# LEGO_VL53L1X_Sensor.net
KiCad netlist of a schematic drawn in Altium Designer
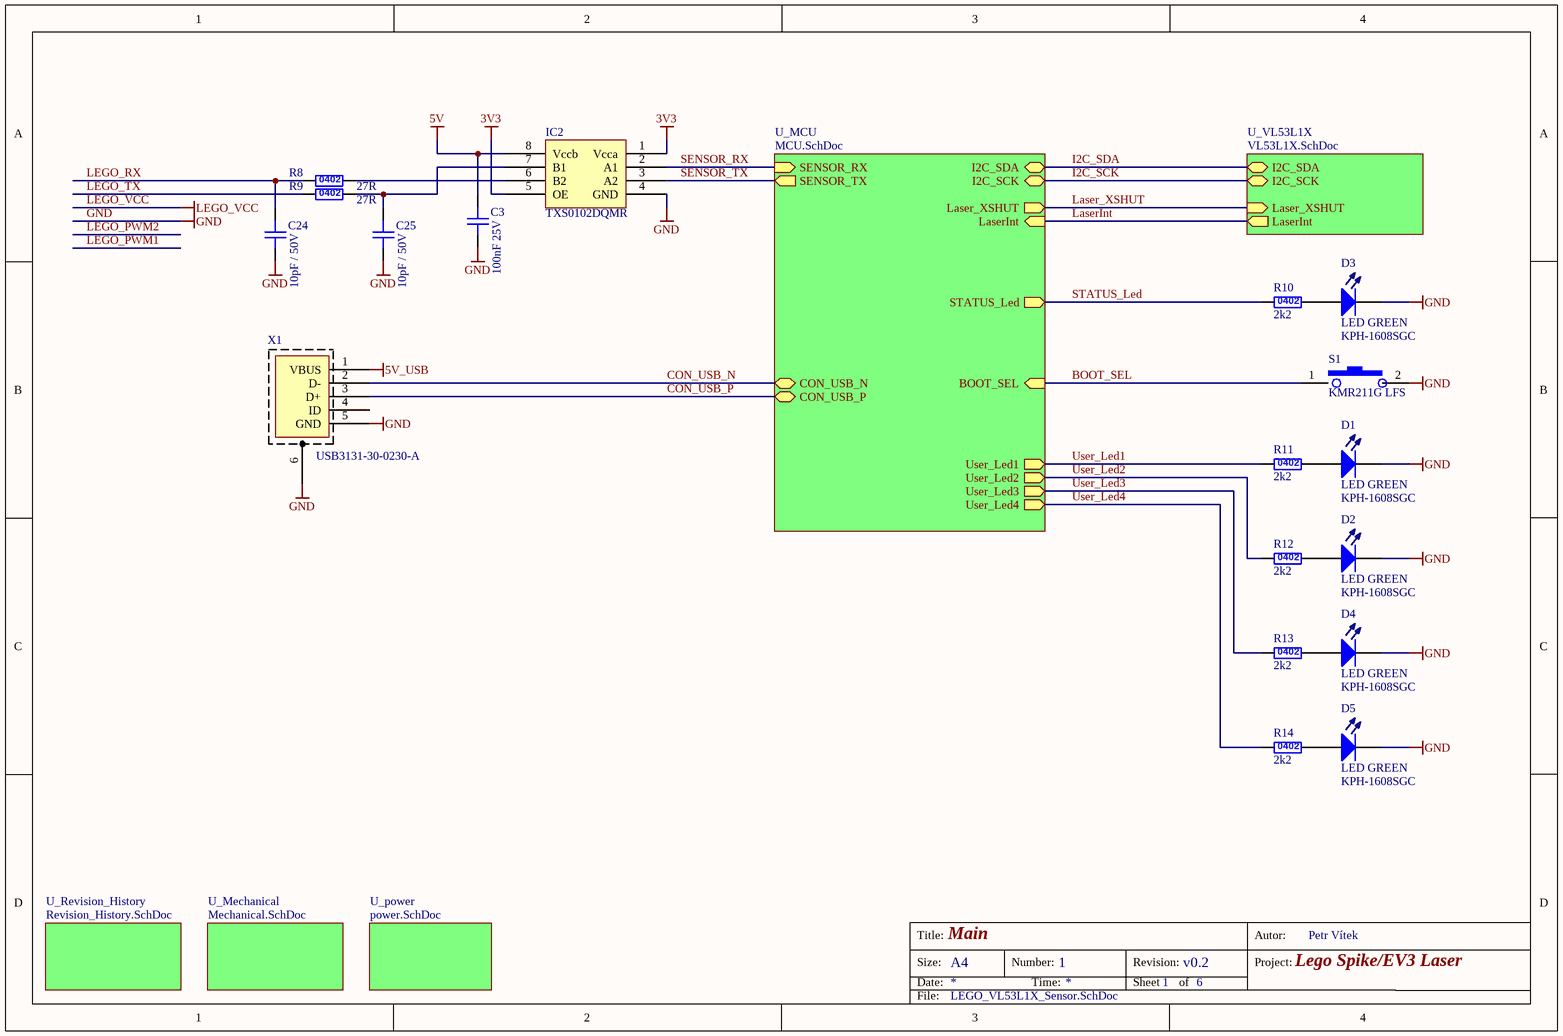
[diagram p0: LEGO_VL53L1X_Sensor.SchDoc]

(export (version "E")
  (design (tool "Eeschema 10.0.6"))
  (components
    (comp (ref "C3")
      (value "100nF 25V")
      (footprint "C0402")
      (description "WALSIN - 0402B104K250CT - CAPACITOR, MLCC, X7R, 0.1UF, 25V, 0402")
      (fields (field (name "Comment") "UniversalCapacitor"))
      (libsource (lib "UTBStockLib") (part "UniversalCapacitor"))
    )
    (comp (ref "C24")
      (value "10pF / 50V")
      (footprint "C0402")
      (fields (field (name "Comment") "UniversalCapacitor"))
      (libsource (lib "UTBStockLib") (part "UniversalCapacitor"))
    )
    (comp (ref "C25")
      (value "10pF / 50V")
      (footprint "C0402")
      (fields (field (name "Comment") "UniversalCapacitor"))
      (libsource (lib "UTBStockLib") (part "UniversalCapacitor"))
    )
    (comp (ref "D1")
      (value "LED GREEN")
      (footprint "LED0603")
      (description "KINGBRIGHT - KPH-1608SGC - LED, GREEN, 12MCD, 568NM, SMD LED 0603 zelená")
      (fields (field (name "ALTIUM_VALUE") "KPH-1608SGC"))
      (libsource (lib "UTBStockLib") (part "LED"))
    )
    (comp (ref "D2")
      (value "LED GREEN")
      (footprint "LED0603")
      (description "KINGBRIGHT - KPH-1608SGC - LED, GREEN, 12MCD, 568NM, SMD LED 0603 zelená")
      (fields (field (name "ALTIUM_VALUE") "KPH-1608SGC"))
      (libsource (lib "UTBStockLib") (part "LED"))
    )
    (comp (ref "D3")
      (value "LED GREEN")
      (footprint "LED0603")
      (description "KINGBRIGHT - KPH-1608SGC - LED, GREEN, 12MCD, 568NM, SMD LED 0603 zelená")
      (fields (field (name "ALTIUM_VALUE") "KPH-1608SGC"))
      (libsource (lib "UTBStockLib") (part "LED"))
    )
    (comp (ref "D4")
      (value "LED GREEN")
      (footprint "LED0603")
      (description "KINGBRIGHT - KPH-1608SGC - LED, GREEN, 12MCD, 568NM, SMD LED 0603 zelená")
      (fields (field (name "ALTIUM_VALUE") "KPH-1608SGC"))
      (libsource (lib "UTBStockLib") (part "LED"))
    )
    (comp (ref "D5")
      (value "LED GREEN")
      (footprint "LED0603")
      (description "KINGBRIGHT - KPH-1608SGC - LED, GREEN, 12MCD, 568NM, SMD LED 0603 zelená")
      (fields (field (name "ALTIUM_VALUE") "KPH-1608SGC"))
      (libsource (lib "UTBStockLib") (part "LED"))
    )
    (comp (ref "IC2")
      (value "TXS0102DQMR")
      (footprint "X2SON-8_1.8x1.2")
      (libsource (lib "UTBStockLib") (part "TXS0102DQMR"))
    )
    (comp (ref "R8")
      (value "27R")
      (footprint "R0402")
      (fields (field (name "Comment") "UniversalResistor0402"))
      (libsource (lib "UTBStockLib") (part "UniversalResistor0402"))
    )
    (comp (ref "R9")
      (value "27R")
      (footprint "R0402")
      (fields (field (name "Comment") "UniversalResistor0402"))
      (libsource (lib "UTBStockLib") (part "UniversalResistor0402"))
    )
    (comp (ref "R10")
      (value "2k2")
      (footprint "R0402")
      (description "VISHAY - CRCW04022K20FKED. - RES, THICK FILM, 2K2, 1%, 0.063W, 0402")
      (fields (field (name "Comment") "UniversalResistor0402"))
      (libsource (lib "UTBStockLib") (part "UniversalResistor0402"))
    )
    (comp (ref "R11")
      (value "2k2")
      (footprint "R0402")
      (description "VISHAY - CRCW04022K20FKED. - RES, THICK FILM, 2K2, 1%, 0.063W, 0402")
      (fields (field (name "Comment") "UniversalResistor0402"))
      (libsource (lib "UTBStockLib") (part "UniversalResistor0402"))
    )
    (comp (ref "R12")
      (value "2k2")
      (footprint "R0402")
      (description "VISHAY - CRCW04022K20FKED. - RES, THICK FILM, 2K2, 1%, 0.063W, 0402")
      (fields (field (name "Comment") "UniversalResistor0402"))
      (libsource (lib "UTBStockLib") (part "UniversalResistor0402"))
    )
    (comp (ref "R13")
      (value "2k2")
      (footprint "R0402")
      (description "VISHAY - CRCW04022K20FKED. - RES, THICK FILM, 2K2, 1%, 0.063W, 0402")
      (fields (field (name "Comment") "UniversalResistor0402"))
      (libsource (lib "UTBStockLib") (part "UniversalResistor0402"))
    )
    (comp (ref "R14")
      (value "2k2")
      (footprint "R0402")
      (description "VISHAY - CRCW04022K20FKED. - RES, THICK FILM, 2K2, 1%, 0.063W, 0402")
      (fields (field (name "Comment") "UniversalResistor0402"))
      (libsource (lib "UTBStockLib") (part "UniversalResistor0402"))
    )
    (comp (ref "S1")
      (value "KMR211G LFS")
      (footprint "ButtonKMR2")
      (description "C & K COMPONENTS - KMR211G LFS - SWITCH, SPST, 0.05A, 32VDC, SMD")
      (fields (field (name "Comment") "PushButton"))
      (libsource (lib "UTBStockLib") (part "PushButton"))
    )
    (comp (ref "X1")
      (value "USB3131-30-0230-A")
      (footprint "USB3131-XX-0230-X")
      (fields (field (name "Comment") "USB"))
      (libsource (lib "UTBStockLib") (part "MUSB"))
    )
  )
  (nets
    (net (code "1") (name "/BOOT_SEL") (class "Default")
      (node (ref "S1") (pin "1") (pinfunction "1_1") (pintype "passive"))
    )
    (net (code "2") (name "/CON_USB_N") (class "Default")
      (node (ref "X1") (pin "2") (pinfunction "D-_2") (pintype "passive"))
    )
    (net (code "3") (name "/CON_USB_P") (class "Default")
      (node (ref "X1") (pin "3") (pinfunction "D+_3") (pintype "passive"))
    )
    (net (code "8") (name "/LEGO_RX") (class "Default")
      (node (ref "C24") (pin "1") (pinfunction "1_1") (pintype "passive"))
      (node (ref "R8") (pin "2") (pinfunction "2_2") (pintype "passive"))
    )
    (net (code "9") (name "/LEGO_TX") (class "Default")
      (node (ref "R9") (pin "2") (pinfunction "2_2") (pintype "passive"))
    )
    (net (code "12") (name "/SENSOR_RX") (class "Default")
      (node (ref "IC2") (pin "2") (pinfunction "A1_2") (pintype "passive"))
    )
    (net (code "13") (name "/SENSOR_TX") (class "Default")
      (node (ref "IC2") (pin "3") (pinfunction "A2_3") (pintype "passive"))
    )
    (net (code "14") (name "/STATUS_Led") (class "Default")
      (node (ref "R10") (pin "2") (pinfunction "2_2") (pintype "passive"))
    )
    (net (code "15") (name "/User_Led1") (class "Default")
      (node (ref "R11") (pin "2") (pinfunction "2_2") (pintype "passive"))
    )
    (net (code "16") (name "/User_Led2") (class "Default")
      (node (ref "R12") (pin "2") (pinfunction "2_2") (pintype "passive"))
    )
    (net (code "17") (name "/User_Led3") (class "Default")
      (node (ref "R13") (pin "2") (pinfunction "2_2") (pintype "passive"))
    )
    (net (code "18") (name "/User_Led4") (class "Default")
      (node (ref "R14") (pin "2") (pinfunction "2_2") (pintype "passive"))
    )
    (net (code "19") (name "3V3") (class "Default")
      (node (ref "IC2") (pin "1") (pinfunction "Vcca_1") (pintype "passive"))
      (node (ref "IC2") (pin "5") (pinfunction "OE_5") (pintype "passive"))
    )
    (net (code "20") (name "5V") (class "Default")
      (node (ref "C3") (pin "2") (pinfunction "2_2") (pintype "passive"))
      (node (ref "IC2") (pin "8") (pinfunction "Vccb_8") (pintype "passive"))
    )
    (net (code "21") (name "5V_USB") (class "Default")
      (node (ref "X1") (pin "1") (pinfunction "VBUS_1") (pintype "passive"))
    )
    (net (code "22") (name "GND") (class "Default")
      (node (ref "C24") (pin "2") (pinfunction "2_2") (pintype "passive"))
      (node (ref "C25") (pin "2") (pinfunction "2_2") (pintype "passive"))
      (node (ref "C3") (pin "1") (pinfunction "1_1") (pintype "passive"))
      (node (ref "D1") (pin "2") (pinfunction "K_2") (pintype "passive"))
      (node (ref "D2") (pin "2") (pinfunction "K_2") (pintype "passive"))
      (node (ref "D3") (pin "2") (pinfunction "K_2") (pintype "passive"))
      (node (ref "D4") (pin "2") (pinfunction "K_2") (pintype "passive"))
      (node (ref "D5") (pin "2") (pinfunction "K_2") (pintype "passive"))
      (node (ref "IC2") (pin "4") (pinfunction "GND_4") (pintype "passive"))
      (node (ref "S1") (pin "2") (pinfunction "2_2") (pintype "passive"))
      (node (ref "X1") (pin "5") (pinfunction "GND_5") (pintype "passive"))
      (node (ref "X1") (pin "6") (pinfunction "6_6") (pintype "passive"))
    )
    (net (code "24") (name "Net-(D1-A)") (class "Default")
      (node (ref "D1") (pin "1") (pinfunction "A_1") (pintype "passive"))
      (node (ref "R11") (pin "1") (pinfunction "1_1") (pintype "passive"))
    )
    (net (code "25") (name "Net-(D2-A)") (class "Default")
      (node (ref "D2") (pin "1") (pinfunction "A_1") (pintype "passive"))
      (node (ref "R12") (pin "1") (pinfunction "1_1") (pintype "passive"))
    )
    (net (code "26") (name "Net-(D3-A)") (class "Default")
      (node (ref "D3") (pin "1") (pinfunction "A_1") (pintype "passive"))
      (node (ref "R10") (pin "1") (pinfunction "1_1") (pintype "passive"))
    )
    (net (code "27") (name "Net-(D4-A)") (class "Default")
      (node (ref "D4") (pin "1") (pinfunction "A_1") (pintype "passive"))
      (node (ref "R13") (pin "1") (pinfunction "1_1") (pintype "passive"))
    )
    (net (code "28") (name "Net-(D5-A)") (class "Default")
      (node (ref "D5") (pin "1") (pinfunction "A_1") (pintype "passive"))
      (node (ref "R14") (pin "1") (pinfunction "1_1") (pintype "passive"))
    )
    (net (code "29") (name "Net-(IC2-B1)") (class "Default")
      (node (ref "C25") (pin "1") (pinfunction "1_1") (pintype "passive"))
      (node (ref "IC2") (pin "7") (pinfunction "B1_7") (pintype "passive"))
      (node (ref "R9") (pin "1") (pinfunction "1_1") (pintype "passive"))
    )
    (net (code "30") (name "Net-(IC2-B2)") (class "Default")
      (node (ref "IC2") (pin "6") (pinfunction "B2_6") (pintype "passive"))
      (node (ref "R8") (pin "1") (pinfunction "1_1") (pintype "passive"))
    )
    (net (code "31") (name "unconnected-(X1-ID-Pad4)") (class "Default")
      (node (ref "X1") (pin "4") (pinfunction "ID_4") (pintype "passive"))
    )
  )
)
